# Sheet2.net
KiCad netlist of a schematic drawn in Altium Designer
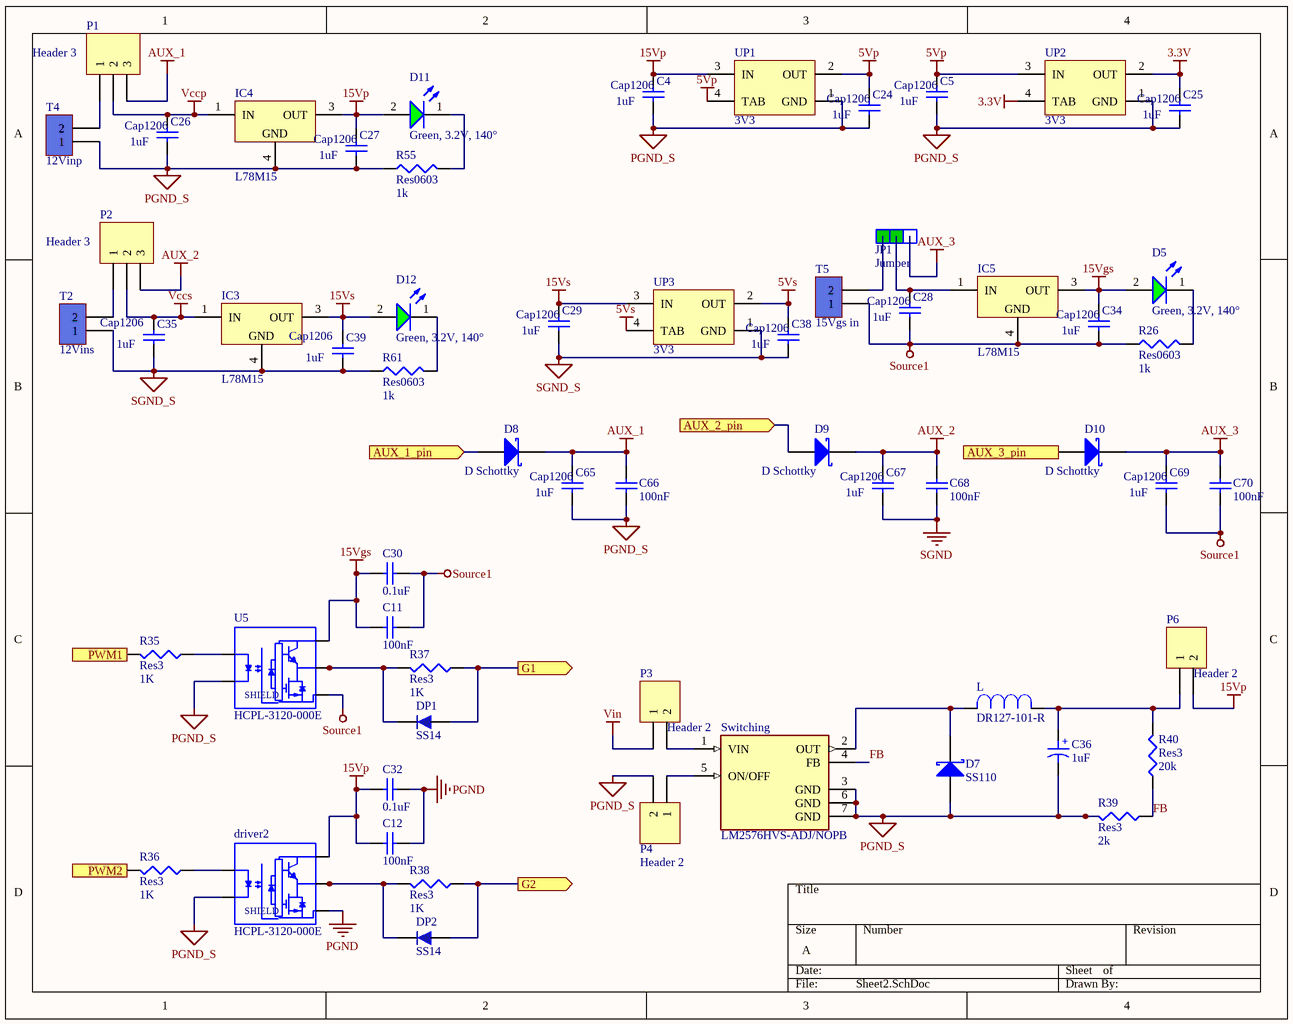
[diagram p0: Sheet2.SchDoc]

(export (version "E")
  (design (tool "Eeschema 10.0.6"))
  (components
    (comp (ref "C4")
      (value "Cap1206")
      (footprint "C1206")
      (description "CAP, CERM, 1uF, 50V, +/-20%, X7R, 1206")
      (fields (field (name "ALTIUM_VALUE") "1uF") (field (name "PUBLISHER") "Altium Limited"))
      (libsource (lib "Miscellaneous Devices") (part "Cap Semi"))
    )
    (comp (ref "C5")
      (value "Cap1206")
      (footprint "C1206")
      (description "CAP, CERM, 1uF, 50V, +/-20%, X7R, 1206")
      (fields (field (name "ALTIUM_VALUE") "1uF") (field (name "PUBLISHER") "Altium Limited"))
      (libsource (lib "Miscellaneous Devices") (part "Cap Semi"))
    )
    (comp (ref "C11")
      (value "100nF")
      (footprint "CAP0603")
      (description "TOTAL CAPACITOR SMD PACK")
      (fields (field (name "DESIGNER") "Abbas Basereh"))
      (libsource (lib "Altium_tehran") (part "CAP SMD PACKAGE"))
    )
    (comp (ref "C12")
      (value "100nF")
      (footprint "CAP0603")
      (description "TOTAL CAPACITOR SMD PACK")
      (fields (field (name "DESIGNER") "Abbas Basereh"))
      (libsource (lib "Altium_tehran") (part "CAP SMD PACKAGE"))
    )
    (comp (ref "C24")
      (value "Cap1206")
      (footprint "C1206")
      (description "CAP, CERM, 1uF, 50V, +/-20%, X7R, 1206")
      (fields (field (name "ALTIUM_VALUE") "1uF") (field (name "PUBLISHER") "Altium Limited"))
      (libsource (lib "Miscellaneous Devices") (part "Cap Semi"))
    )
    (comp (ref "C25")
      (value "Cap1206")
      (footprint "C1206")
      (description "CAP, CERM, 1uF, 50V, +/-20%, X7R, 1206")
      (fields (field (name "ALTIUM_VALUE") "1uF") (field (name "PUBLISHER") "Altium Limited"))
      (libsource (lib "Miscellaneous Devices") (part "Cap Semi"))
    )
    (comp (ref "C26")
      (value "Cap1206")
      (footprint "C1206")
      (description "CAP, CERM, 1uF, 50V, +/-20%, X7R, 1206")
      (fields (field (name "ALTIUM_VALUE") "1uF") (field (name "PUBLISHER") "Altium Limited"))
      (libsource (lib "Miscellaneous Devices") (part "Cap Semi"))
    )
    (comp (ref "C27")
      (value "Cap1206")
      (footprint "C1206")
      (description "CAP, CERM, 1uF, 50V, +/-20%, X7R, 1206")
      (fields (field (name "ALTIUM_VALUE") "1uF") (field (name "PUBLISHER") "Altium Limited"))
      (libsource (lib "Miscellaneous Devices") (part "Cap Semi"))
    )
    (comp (ref "C28")
      (value "Cap1206")
      (footprint "C1206")
      (description "CAP, CERM, 1uF, 50V, +/-20%, X7R, 1206")
      (fields (field (name "ALTIUM_VALUE") "1uF") (field (name "PUBLISHER") "Altium Limited"))
      (libsource (lib "Miscellaneous Devices") (part "Cap Semi"))
    )
    (comp (ref "C29")
      (value "Cap1206")
      (footprint "C1206")
      (description "CAP, CERM, 1uF, 50V, +/-20%, X7R, 1206")
      (fields (field (name "ALTIUM_VALUE") "1uF") (field (name "PUBLISHER") "Altium Limited"))
      (libsource (lib "Miscellaneous Devices") (part "Cap Semi"))
    )
    (comp (ref "C30")
      (value "0.1uF")
      (footprint "CAPC4817X12N")
      (description "CAP 1206")
      (fields (field (name "DESIGNER") "Abbas Basereh"))
      (libsource (lib "Altium_tehran") (part "CAP SMD 1206"))
    )
    (comp (ref "C32")
      (value "0.1uF")
      (footprint "CAPC4817X12N")
      (description "CAP 1206")
      (fields (field (name "DESIGNER") "Abbas Basereh"))
      (libsource (lib "Altium_tehran") (part "CAP SMD 1206"))
    )
    (comp (ref "C34")
      (value "Cap1206")
      (footprint "C1206")
      (description "CAP, CERM, 1uF, 50V, +/-20%, X7R, 1206")
      (fields (field (name "ALTIUM_VALUE") "1uF") (field (name "PUBLISHER") "Altium Limited"))
      (libsource (lib "Miscellaneous Devices") (part "Cap Semi"))
    )
    (comp (ref "C35")
      (value "Cap1206")
      (footprint "C1206")
      (description "CAP, CERM, 1uF, 50V, +/-20%, X7R, 1206")
      (fields (field (name "ALTIUM_VALUE") "1uF") (field (name "PUBLISHER") "Altium Limited"))
      (libsource (lib "Miscellaneous Devices") (part "Cap Semi"))
    )
    (comp (ref "C36")
      (value "1uF")
      (footprint "Cap electrolitic radial 8x12-3.5")
      (description "Cap electrolitic radial")
      (fields (field (name "DESIGNER") "Abbas Basereh"))
      (libsource (lib "Altium_tehran") (part "Cap ELECTROLITIC TOTAL SIZE"))
    )
    (comp (ref "C38")
      (value "Cap1206")
      (footprint "C1206")
      (description "CAP, CERM, 1uF, 50V, +/-20%, X7R, 1206")
      (fields (field (name "ALTIUM_VALUE") "1uF") (field (name "PUBLISHER") "Altium Limited"))
      (libsource (lib "Miscellaneous Devices") (part "Cap Semi"))
    )
    (comp (ref "C39")
      (value "Cap1206")
      (footprint "C1206")
      (description "CAP, CERM, 1uF, 50V, +/-20%, X7R, 1206")
      (fields (field (name "ALTIUM_VALUE") "1uF") (field (name "PUBLISHER") "Altium Limited"))
      (libsource (lib "Miscellaneous Devices") (part "Cap Semi"))
    )
    (comp (ref "C65")
      (value "Cap1206")
      (footprint "C1206")
      (description "CAP, CERM, 1uF, 50V, +/-20%, X7R, 1206")
      (fields (field (name "ALTIUM_VALUE") "1uF") (field (name "PUBLISHER") "Altium Limited"))
      (libsource (lib "Miscellaneous Devices") (part "Cap Semi"))
    )
    (comp (ref "C66")
      (value "100nF")
      (footprint "Cap SMD 100UF 35~50v")
      (description "TOTAL CAPACITOR SMD PACK")
      (fields (field (name "DESIGNER") "Abbas Basereh"))
      (libsource (lib "Altium_tehran") (part "CAP SMD PACKAGE"))
    )
    (comp (ref "C67")
      (value "Cap1206")
      (footprint "C1206")
      (description "CAP, CERM, 1uF, 50V, +/-20%, X7R, 1206")
      (fields (field (name "ALTIUM_VALUE") "1uF") (field (name "PUBLISHER") "Altium Limited"))
      (libsource (lib "Miscellaneous Devices") (part "Cap Semi"))
    )
    (comp (ref "C68")
      (value "100nF")
      (footprint "Cap SMD 100UF 35~50v")
      (description "TOTAL CAPACITOR SMD PACK")
      (fields (field (name "DESIGNER") "Abbas Basereh"))
      (libsource (lib "Altium_tehran") (part "CAP SMD PACKAGE"))
    )
    (comp (ref "C69")
      (value "Cap1206")
      (footprint "C1206")
      (description "CAP, CERM, 1uF, 50V, +/-20%, X7R, 1206")
      (fields (field (name "ALTIUM_VALUE") "1uF") (field (name "PUBLISHER") "Altium Limited"))
      (libsource (lib "Miscellaneous Devices") (part "Cap Semi"))
    )
    (comp (ref "C70")
      (value "100nF")
      (footprint "Cap SMD 100UF 35~50v")
      (description "TOTAL CAPACITOR SMD PACK")
      (fields (field (name "DESIGNER") "Abbas Basereh"))
      (libsource (lib "Altium_tehran") (part "CAP SMD PACKAGE"))
    )
    (comp (ref "D5")
      (value "Green, 3.2V, 140°")
      (footprint "WL-SMCW_0805_150080xx75000")
      (description "WL-SMCW Mono-color Chip LED Waterclear, SMT, size 0805, Green, 3.2V, 140°")
      (fields
        (field (name "MANUFACTURER PART NUMBER") "150080GS75000")
        (field (name "MANUFACTURER") "Wurth Elektronik")
      )
      (libsource (lib "150060AS75000_Altium_WL-SMCW_rev24b") (part "150080GS75000"))
    )
    (comp (ref "D7")
      (value "SS110")
      (footprint "SMB")
      (description "Schottky Diode")
      (fields (field (name "PUBLISHER") "Altium Limited"))
      (libsource (lib "Miscellaneous Devices") (part "D Schottky"))
    )
    (comp (ref "D8")
      (value "D Schottky")
      (footprint "SMB")
      (description "Schottky Diode")
      (fields (field (name "PUBLISHER") "Altium Limited"))
      (libsource (lib "Miscellaneous Devices") (part "D Schottky"))
    )
    (comp (ref "D9")
      (value "D Schottky")
      (footprint "SMB")
      (description "Schottky Diode")
      (fields (field (name "PUBLISHER") "Altium Limited"))
      (libsource (lib "Miscellaneous Devices") (part "D Schottky"))
    )
    (comp (ref "D10")
      (value "D Schottky")
      (footprint "SMB")
      (description "Schottky Diode")
      (fields (field (name "PUBLISHER") "Altium Limited"))
      (libsource (lib "Miscellaneous Devices") (part "D Schottky"))
    )
    (comp (ref "D11")
      (value "Green, 3.2V, 140°")
      (footprint "WL-SMCW_0805_150080xx75000")
      (description "WL-SMCW Mono-color Chip LED Waterclear, SMT, size 0805, Green, 3.2V, 140°")
      (fields
        (field (name "MANUFACTURER PART NUMBER") "150080GS75000")
        (field (name "MANUFACTURER") "Wurth Elektronik")
      )
      (libsource (lib "150060AS75000_Altium_WL-SMCW_rev24b") (part "150080GS75000"))
    )
    (comp (ref "D12")
      (value "Green, 3.2V, 140°")
      (footprint "WL-SMCW_0805_150080xx75000")
      (description "WL-SMCW Mono-color Chip LED Waterclear, SMT, size 0805, Green, 3.2V, 140°")
      (fields
        (field (name "MANUFACTURER PART NUMBER") "150080GS75000")
        (field (name "MANUFACTURER") "Wurth Elektronik")
      )
      (libsource (lib "150060AS75000_Altium_WL-SMCW_rev24b") (part "150080GS75000"))
    )
    (comp (ref "DP1")
      (value "SS14")
      (footprint "430X270D")
      (description "Schottkey Rectifiers")
      (fields (field (name "DESIGNER") "Abbas Basereh"))
      (libsource (lib "Altium_tehran") (part "1N5819"))
    )
    (comp (ref "DP2")
      (value "SS14")
      (footprint "430X270D")
      (description "Schottkey Rectifiers")
      (fields (field (name "DESIGNER") "Abbas Basereh"))
      (libsource (lib "Altium_tehran") (part "1N5819"))
    )
    (comp (ref "driver2")
      (value "HCPL-3120-000E")
      (footprint "DIP762W65P254L990H470Q8")
      (description "2.5A Gate Driver Optical Coupling 3750Vrms 1 Channel 8-DIP")
      (fields (field (name "MF") "Broadcom Limited"))
      (libsource (lib "HCPL-3120-000E") (part "HCPL-3120-000E"))
    )
    (comp (ref "IC3")
      (value "L78M15")
      (footprint "TO-252")
      (description "Precision 500mA Regulator")
      (libsource (lib "Altium_tehran") (part "L78M05"))
    )
    (comp (ref "IC4")
      (value "L78M15")
      (footprint "TO-252")
      (description "Precision 500mA Regulator")
      (libsource (lib "Altium_tehran") (part "L78M05"))
    )
    (comp (ref "IC5")
      (value "L78M15")
      (footprint "TO-252")
      (description "Precision 500mA Regulator")
      (libsource (lib "Altium_tehran") (part "L78M05"))
    )
    (comp (ref "JP1")
      (value "Jumper")
      (footprint "jumper selector")
      (description "Jumper Selector")
      (libsource (lib "Altium_tehran") (part "Jumper Selector"))
    )
    (comp (ref "L")
      (value "DR127-101-R")
      (footprint "INDM125125X800N")
      (description "100ÂµH Shielded Wirewound Inductor 1.96A 163mOhm Nonstandard")
      (fields (field (name "MF") "Eaton"))
      (libsource (lib "DR127-101-R") (part "DR127-101-R"))
    )
    (comp (ref "P1")
      (value "Header 3")
      (footprint "HDR1X3")
      (description "Header, 3-Pin")
      (fields (field (name "PUBLISHER") "Altium Limited"))
      (libsource (lib "Altium_tehran") (part "Header 3"))
    )
    (comp (ref "P2")
      (value "Header 3")
      (footprint "HDR1X3")
      (description "Header, 3-Pin")
      (fields (field (name "PUBLISHER") "Altium Limited"))
      (libsource (lib "Altium_tehran") (part "Header 3"))
    )
    (comp (ref "P3")
      (value "Header 2")
      (footprint "HDR1X2")
      (description "Header, 2-Pin, 100mill")
      (fields (field (name "PUBLISHER") "Altium Limited"))
      (libsource (lib "Miscellaneous Connectors") (part "Header 2"))
    )
    (comp (ref "P4")
      (value "Header 2")
      (footprint "HDR1X2")
      (description "Header, 2-Pin, 100mill")
      (fields (field (name "PUBLISHER") "Altium Limited"))
      (libsource (lib "") (part "Header 2_1"))
    )
    (comp (ref "P6")
      (value "Header 2")
      (footprint "HDR1X2")
      (description "Header, 2-Pin, 100mill")
      (fields (field (name "PUBLISHER") "Altium Limited"))
      (libsource (lib "Miscellaneous Connectors") (part "Header 2"))
    )
    (comp (ref "R26")
      (value "Res0603")
      (footprint "J1-0603")
      (description "RES, 1k ohm, 1%, 0.1W, 0603")
      (fields (field (name "ALTIUM_VALUE") "1k") (field (name "PUBLISHER") "Altium Limited"))
      (libsource (lib "Miscellaneous Devices") (part "Res3"))
    )
    (comp (ref "R35")
      (value "Res3")
      (footprint "J1-0603")
      (description "Resistor")
      (fields (field (name "ALTIUM_VALUE") "1K") (field (name "PUBLISHER") "Altium Limited"))
      (libsource (lib "Miscellaneous Devices") (part "Res3"))
    )
    (comp (ref "R36")
      (value "Res3")
      (footprint "J1-0603")
      (description "Resistor")
      (fields (field (name "ALTIUM_VALUE") "1K") (field (name "PUBLISHER") "Altium Limited"))
      (libsource (lib "Miscellaneous Devices") (part "Res3"))
    )
    (comp (ref "R37")
      (value "Res3")
      (footprint "J1-0603")
      (description "Resistor")
      (fields (field (name "ALTIUM_VALUE") "1K") (field (name "PUBLISHER") "Altium Limited"))
      (libsource (lib "Miscellaneous Devices") (part "Res3"))
    )
    (comp (ref "R38")
      (value "Res3")
      (footprint "J1-0603")
      (description "Resistor")
      (fields (field (name "ALTIUM_VALUE") "1K") (field (name "PUBLISHER") "Altium Limited"))
      (libsource (lib "Miscellaneous Devices") (part "Res3"))
    )
    (comp (ref "R39")
      (value "Res3")
      (footprint "J1-0603")
      (description "Resistor")
      (fields (field (name "ALTIUM_VALUE") "2k") (field (name "PUBLISHER") "Altium Limited"))
      (libsource (lib "Miscellaneous Devices") (part "Res3"))
    )
    (comp (ref "R40")
      (value "Res3")
      (footprint "J1-0603")
      (description "Resistor")
      (fields (field (name "ALTIUM_VALUE") "20k") (field (name "PUBLISHER") "Altium Limited"))
      (libsource (lib "Miscellaneous Devices") (part "Res3"))
    )
    (comp (ref "R55")
      (value "Res0603")
      (footprint "J1-0603")
      (description "RES, 1k ohm, 1%, 0.1W, 0603")
      (fields (field (name "ALTIUM_VALUE") "1k") (field (name "PUBLISHER") "Altium Limited"))
      (libsource (lib "Miscellaneous Devices") (part "Res3"))
    )
    (comp (ref "R61")
      (value "Res0603")
      (footprint "J1-0603")
      (description "RES, 1k ohm, 1%, 0.1W, 0603")
      (fields (field (name "ALTIUM_VALUE") "1k") (field (name "PUBLISHER") "Altium Limited"))
      (libsource (lib "Miscellaneous Devices") (part "Res3"))
    )
    (comp (ref "Switching")
      (value "LM2576HVS-ADJ/NOPB")
      (footprint "REG_LM2576HVS-ADJ/NOPB")
      (fields (field (name "MF") "Texas Instruments"))
      (libsource (lib "LM2576HVS-ADJ_NOPB") (part "LM2576HVS-ADJ/NOPB"))
    )
    (comp (ref "T2")
      (value "12Vins")
      (footprint "KF301 2PIN")
      (description "Terminal 2 Pin 250VAC 16A")
      (fields (field (name "DESIGNER") "Abbas Basereh"))
      (libsource (lib "Altium_tehran") (part "KF301-2Pin_Terminal"))
    )
    (comp (ref "T4")
      (value "12Vinp")
      (footprint "KF301 2PIN")
      (description "Terminal 2 Pin 250VAC 16A")
      (fields (field (name "DESIGNER") "Abbas Basereh"))
      (libsource (lib "Altium_tehran") (part "KF301-2Pin_Terminal"))
    )
    (comp (ref "T5")
      (value "15Vgs in")
      (footprint "KF301 2PIN")
      (description "Terminal 2 Pin 250VAC 16A")
      (fields (field (name "DESIGNER") "Abbas Basereh"))
      (libsource (lib "Altium_tehran") (part "KF301-2Pin_Terminal"))
    )
    (comp (ref "U5")
      (value "HCPL-3120-000E")
      (footprint "DIP762W65P254L990H470Q8")
      (description "2.5A Gate Driver Optical Coupling 3750Vrms 1 Channel 8-DIP")
      (fields (field (name "MF") "Broadcom Limited"))
      (libsource (lib "HCPL-3120-000E") (part "HCPL-3120-000E"))
    )
    (comp (ref "UP1")
      (value "3V3")
      (footprint "SOT223")
      (description "x.x Volt, 800mA Low-Dropout Linear Regulator, 4-pin SOT-223")
      (fields (field (name "DESIGNER") "Ali Hafizi"))
      (libsource (lib "Altium_tehran") (part "AMS1117-x.x"))
    )
    (comp (ref "UP2")
      (value "3V3")
      (footprint "SOT223")
      (description "x.x Volt, 800mA Low-Dropout Linear Regulator, 4-pin SOT-223")
      (fields (field (name "DESIGNER") "Ali Hafizi"))
      (libsource (lib "Altium_tehran") (part "AMS1117-x.x"))
    )
    (comp (ref "UP3")
      (value "3V3")
      (footprint "SOT223")
      (description "x.x Volt, 800mA Low-Dropout Linear Regulator, 4-pin SOT-223")
      (fields (field (name "DESIGNER") "Ali Hafizi"))
      (libsource (lib "Altium_tehran") (part "AMS1117-x.x"))
    )
  )
  (nets
    (net (code "1") (name "/AUX_1_pin") (class "Default")
      (node (ref "D8") (pin "1") (pinfunction "A_1") (pintype "passive"))
    )
    (net (code "2") (name "/AUX_2_pin") (class "Default")
      (node (ref "D9") (pin "1") (pinfunction "A_1") (pintype "passive"))
    )
    (net (code "3") (name "/AUX_3_pin") (class "Default")
      (node (ref "D10") (pin "1") (pinfunction "A_1") (pintype "passive"))
    )
    (net (code "4") (name "/FB") (class "Default")
      (node (ref "R39") (pin "1") (pinfunction "1_1") (pintype "passive"))
      (node (ref "R40") (pin "1") (pinfunction "1_1") (pintype "passive"))
      (node (ref "Switching") (pin "4") (pinfunction "FB_4") (pintype "passive"))
    )
    (net (code "5") (name "/G1") (class "Default")
      (node (ref "DP1") (pin "1") (pintype "passive"))
      (node (ref "R37") (pin "1") (pinfunction "1_1") (pintype "passive"))
    )
    (net (code "6") (name "/G2") (class "Default")
      (node (ref "DP2") (pin "1") (pintype "passive"))
      (node (ref "R38") (pin "1") (pinfunction "1_1") (pintype "passive"))
    )
    (net (code "7") (name "/PWM1") (class "Default")
      (node (ref "R35") (pin "2") (pinfunction "2_2") (pintype "passive"))
    )
    (net (code "8") (name "/PWM2") (class "Default")
      (node (ref "R36") (pin "2") (pinfunction "2_2") (pintype "passive"))
    )
    (net (code "9") (name "3.3V") (class "Default")
      (node (ref "C25") (pin "1") (pinfunction "1_1") (pintype "passive"))
      (node (ref "UP2") (pin "2") (pinfunction "OUT_2") (pintype "power_in"))
      (node (ref "UP2") (pin "4") (pinfunction "TAB_4") (pintype "power_in"))
    )
    (net (code "10") (name "5Vp") (class "Default")
      (node (ref "C24") (pin "1") (pinfunction "1_1") (pintype "passive"))
      (node (ref "C5") (pin "1") (pinfunction "1_1") (pintype "passive"))
      (node (ref "UP1") (pin "2") (pinfunction "OUT_2") (pintype "power_in"))
      (node (ref "UP1") (pin "4") (pinfunction "TAB_4") (pintype "power_in"))
      (node (ref "UP2") (pin "3") (pinfunction "IN_3") (pintype "power_in"))
    )
    (net (code "11") (name "5Vs") (class "Default")
      (node (ref "C38") (pin "1") (pinfunction "1_1") (pintype "passive"))
      (node (ref "UP3") (pin "2") (pinfunction "OUT_2") (pintype "power_in"))
      (node (ref "UP3") (pin "4") (pinfunction "TAB_4") (pintype "power_in"))
    )
    (net (code "12") (name "15Vgs") (class "Default")
      (node (ref "C11") (pin "2") (pinfunction "2_2") (pintype "passive"))
      (node (ref "C30") (pin "2") (pinfunction "2_2") (pintype "passive"))
      (node (ref "C34") (pin "1") (pinfunction "1_1") (pintype "passive"))
      (node (ref "D5") (pin "2") (pinfunction "A_2") (pintype "passive"))
      (node (ref "IC5") (pin "3") (pinfunction "OUT_3") (pintype "power_in"))
      (node (ref "U5") (pin "8") (pinfunction "VCC_8") (pintype "passive"))
    )
    (net (code "13") (name "15Vp") (class "Default")
      (node (ref "C12") (pin "2") (pinfunction "2_2") (pintype "passive"))
      (node (ref "C27") (pin "1") (pinfunction "1_1") (pintype "passive"))
      (node (ref "C32") (pin "2") (pinfunction "2_2") (pintype "passive"))
      (node (ref "C4") (pin "1") (pinfunction "1_1") (pintype "passive"))
      (node (ref "D11") (pin "2") (pinfunction "A_2") (pintype "passive"))
      (node (ref "IC4") (pin "3") (pinfunction "OUT_3") (pintype "power_in"))
      (node (ref "P6") (pin "2") (pinfunction "2_2") (pintype "passive"))
      (node (ref "UP1") (pin "3") (pinfunction "IN_3") (pintype "power_in"))
      (node (ref "driver2") (pin "8") (pinfunction "VCC_8") (pintype "passive"))
    )
    (net (code "14") (name "15Vs") (class "Default")
      (node (ref "C29") (pin "1") (pinfunction "1_1") (pintype "passive"))
      (node (ref "C39") (pin "1") (pinfunction "1_1") (pintype "passive"))
      (node (ref "D12") (pin "2") (pinfunction "A_2") (pintype "passive"))
      (node (ref "IC3") (pin "3") (pinfunction "OUT_3") (pintype "power_in"))
      (node (ref "UP3") (pin "3") (pinfunction "IN_3") (pintype "power_in"))
    )
    (net (code "15") (name "AUX_1") (class "Default")
      (node (ref "C65") (pin "1") (pinfunction "1_1") (pintype "passive"))
      (node (ref "C66") (pin "2") (pinfunction "2_2") (pintype "passive"))
      (node (ref "D8") (pin "2") (pinfunction "K_2") (pintype "passive"))
      (node (ref "P1") (pin "3") (pinfunction "3_3") (pintype "passive"))
    )
    (net (code "16") (name "AUX_2") (class "Default")
      (node (ref "C67") (pin "1") (pinfunction "1_1") (pintype "passive"))
      (node (ref "C68") (pin "2") (pinfunction "2_2") (pintype "passive"))
      (node (ref "D9") (pin "2") (pinfunction "K_2") (pintype "passive"))
      (node (ref "P2") (pin "3") (pinfunction "3_3") (pintype "passive"))
    )
    (net (code "17") (name "AUX_3") (class "Default")
      (node (ref "C69") (pin "1") (pinfunction "1_1") (pintype "passive"))
      (node (ref "C70") (pin "2") (pinfunction "2_2") (pintype "passive"))
      (node (ref "D10") (pin "2") (pinfunction "K_2") (pintype "passive"))
      (node (ref "JP1") (pin "3") (pinfunction "3_3") (pintype "passive"))
    )
    (net (code "18") (name "Net-(C36-Pad1)") (class "Default")
      (node (ref "C36") (pin "1") (pinfunction "1_1") (pintype "passive"))
      (node (ref "L") (pin "1") (pinfunction "1_1") (pintype "passive"))
      (node (ref "P6") (pin "1") (pinfunction "1_1") (pintype "passive"))
      (node (ref "R40") (pin "2") (pinfunction "2_2") (pintype "passive"))
    )
    (net (code "19") (name "Net-(D5-K)") (class "Default")
      (node (ref "D5") (pin "1") (pinfunction "K_1") (pintype "passive"))
      (node (ref "R26") (pin "2") (pinfunction "2_2") (pintype "passive"))
    )
    (net (code "20") (name "Net-(D7-K)") (class "Default")
      (node (ref "D7") (pin "2") (pinfunction "K_2") (pintype "passive"))
      (node (ref "L") (pin "2") (pinfunction "2_2") (pintype "passive"))
      (node (ref "Switching") (pin "2") (pinfunction "OUT_2") (pintype "output"))
    )
    (net (code "21") (name "Net-(D11-K)") (class "Default")
      (node (ref "D11") (pin "1") (pinfunction "K_1") (pintype "passive"))
      (node (ref "R55") (pin "2") (pinfunction "2_2") (pintype "passive"))
    )
    (net (code "22") (name "Net-(D12-K)") (class "Default")
      (node (ref "D12") (pin "1") (pinfunction "K_1") (pintype "passive"))
      (node (ref "R61") (pin "2") (pinfunction "2_2") (pintype "passive"))
    )
    (net (code "23") (name "Net-(DP1-Pad2)") (class "Default")
      (node (ref "DP1") (pin "2") (pintype "passive"))
      (node (ref "R37") (pin "2") (pinfunction "2_2") (pintype "passive"))
      (node (ref "U5") (pin "6") (pinfunction "VO_6") (pintype "passive"))
      (node (ref "U5") (pin "7") (pinfunction "VO_7") (pintype "passive"))
    )
    (net (code "24") (name "Net-(DP2-Pad2)") (class "Default")
      (node (ref "DP2") (pin "2") (pintype "passive"))
      (node (ref "R38") (pin "2") (pinfunction "2_2") (pintype "passive"))
      (node (ref "driver2") (pin "6") (pinfunction "VO_6") (pintype "passive"))
      (node (ref "driver2") (pin "7") (pinfunction "VO_7") (pintype "passive"))
    )
    (net (code "25") (name "Net-(IC5-IN)") (class "Default")
      (node (ref "C28") (pin "1") (pinfunction "1_1") (pintype "passive"))
      (node (ref "IC5") (pin "1") (pinfunction "IN_1") (pintype "power_in"))
      (node (ref "JP1") (pin "2") (pinfunction "2_2") (pintype "passive"))
    )
    (net (code "26") (name "Net-(JP1-Pad1)") (class "Default")
      (node (ref "JP1") (pin "1") (pinfunction "1_1") (pintype "passive"))
      (node (ref "T5") (pin "2") (pinfunction "2_2") (pintype "passive"))
    )
    (net (code "27") (name "Net-(P1-Pad1)") (class "Default")
      (node (ref "P1") (pin "1") (pinfunction "1_1") (pintype "passive"))
      (node (ref "T4") (pin "2") (pinfunction "2_2") (pintype "passive"))
    )
    (net (code "28") (name "Net-(P2-Pad1)") (class "Default")
      (node (ref "P2") (pin "1") (pinfunction "1_1") (pintype "passive"))
      (node (ref "T2") (pin "2") (pinfunction "2_2") (pintype "passive"))
    )
    (net (code "29") (name "Net-(Switching-ON{slash}OFF)") (class "Default")
      (node (ref "P4") (pin "1") (pinfunction "1_1") (pintype "passive"))
      (node (ref "Switching") (pin "5") (pinfunction "ON/OFF_5") (pintype "input"))
    )
    (net (code "30") (name "Net-(Switching-VIN)") (class "Default")
      (node (ref "P3") (pin "2") (pinfunction "2_2") (pintype "passive"))
      (node (ref "Switching") (pin "1") (pinfunction "VIN_1") (pintype "input"))
    )
    (net (code "31") (name "Net-(U5-ANODE)") (class "Default")
      (node (ref "R35") (pin "1") (pinfunction "1_1") (pintype "passive"))
      (node (ref "U5") (pin "2") (pinfunction "ANODE_2") (pintype "passive"))
    )
    (net (code "32") (name "Net-(driver2-ANODE)") (class "Default")
      (node (ref "R36") (pin "1") (pinfunction "1_1") (pintype "passive"))
      (node (ref "driver2") (pin "2") (pinfunction "ANODE_2") (pintype "passive"))
    )
    (net (code "33") (name "PGND") (class "Default")
      (node (ref "C12") (pin "1") (pinfunction "1_1") (pintype "passive"))
      (node (ref "C32") (pin "1") (pinfunction "1_1") (pintype "passive"))
      (node (ref "driver2") (pin "5") (pinfunction "VEE_5") (pintype "passive"))
    )
    (net (code "34") (name "PGND_S") (class "Default")
      (node (ref "C24") (pin "2") (pinfunction "2_2") (pintype "passive"))
      (node (ref "C25") (pin "2") (pinfunction "2_2") (pintype "passive"))
      (node (ref "C26") (pin "2") (pinfunction "2_2") (pintype "passive"))
      (node (ref "C27") (pin "2") (pinfunction "2_2") (pintype "passive"))
      (node (ref "C36") (pin "2") (pinfunction "2_2") (pintype "passive"))
      (node (ref "C4") (pin "2") (pinfunction "2_2") (pintype "passive"))
      (node (ref "C5") (pin "2") (pinfunction "2_2") (pintype "passive"))
      (node (ref "C65") (pin "2") (pinfunction "2_2") (pintype "passive"))
      (node (ref "C66") (pin "1") (pinfunction "1_1") (pintype "passive"))
      (node (ref "D7") (pin "1") (pinfunction "A_1") (pintype "passive"))
      (node (ref "IC4") (pin "4") (pinfunction "GND_4") (pintype "power_in"))
      (node (ref "P4") (pin "2") (pinfunction "2_2") (pintype "passive"))
      (node (ref "R39") (pin "2") (pinfunction "2_2") (pintype "passive"))
      (node (ref "R55") (pin "1") (pinfunction "1_1") (pintype "passive"))
      (node (ref "Switching") (pin "3") (pinfunction "GND_3") (pintype "power_in"))
      (node (ref "Switching") (pin "6") (pinfunction "GND_6") (pintype "power_in"))
      (node (ref "Switching") (pin "7") (pinfunction "GND_7") (pintype "power_in"))
      (node (ref "T4") (pin "1") (pinfunction "1_1") (pintype "passive"))
      (node (ref "U5") (pin "3") (pinfunction "CATHODE_3") (pintype "passive"))
      (node (ref "UP1") (pin "1") (pinfunction "GND_1") (pintype "power_in"))
      (node (ref "UP2") (pin "1") (pinfunction "GND_1") (pintype "power_in"))
      (node (ref "driver2") (pin "3") (pinfunction "CATHODE_3") (pintype "passive"))
    )
    (net (code "35") (name "SGND") (class "Default")
      (node (ref "C67") (pin "2") (pinfunction "2_2") (pintype "passive"))
      (node (ref "C68") (pin "1") (pinfunction "1_1") (pintype "passive"))
    )
    (net (code "36") (name "SGND_S") (class "Default")
      (node (ref "C29") (pin "2") (pinfunction "2_2") (pintype "passive"))
      (node (ref "C35") (pin "2") (pinfunction "2_2") (pintype "passive"))
      (node (ref "C38") (pin "2") (pinfunction "2_2") (pintype "passive"))
      (node (ref "C39") (pin "2") (pinfunction "2_2") (pintype "passive"))
      (node (ref "IC3") (pin "4") (pinfunction "GND_4") (pintype "power_in"))
      (node (ref "R61") (pin "1") (pinfunction "1_1") (pintype "passive"))
      (node (ref "T2") (pin "1") (pinfunction "1_1") (pintype "passive"))
      (node (ref "UP3") (pin "1") (pinfunction "GND_1") (pintype "power_in"))
    )
    (net (code "37") (name "Source1") (class "Default")
      (node (ref "C11") (pin "1") (pinfunction "1_1") (pintype "passive"))
      (node (ref "C28") (pin "2") (pinfunction "2_2") (pintype "passive"))
      (node (ref "C30") (pin "1") (pinfunction "1_1") (pintype "passive"))
      (node (ref "C34") (pin "2") (pinfunction "2_2") (pintype "passive"))
      (node (ref "C69") (pin "2") (pinfunction "2_2") (pintype "passive"))
      (node (ref "C70") (pin "1") (pinfunction "1_1") (pintype "passive"))
      (node (ref "IC5") (pin "4") (pinfunction "GND_4") (pintype "power_in"))
      (node (ref "R26") (pin "1") (pinfunction "1_1") (pintype "passive"))
      (node (ref "T5") (pin "1") (pinfunction "1_1") (pintype "passive"))
      (node (ref "U5") (pin "5") (pinfunction "VEE_5") (pintype "passive"))
    )
    (net (code "38") (name "Vccp") (class "Default")
      (node (ref "C26") (pin "1") (pinfunction "1_1") (pintype "passive"))
      (node (ref "IC4") (pin "1") (pinfunction "IN_1") (pintype "power_in"))
      (node (ref "P1") (pin "2") (pinfunction "2_2") (pintype "passive"))
    )
    (net (code "39") (name "Vccs") (class "Default")
      (node (ref "C35") (pin "1") (pinfunction "1_1") (pintype "passive"))
      (node (ref "IC3") (pin "1") (pinfunction "IN_1") (pintype "power_in"))
      (node (ref "P2") (pin "2") (pinfunction "2_2") (pintype "passive"))
    )
    (net (code "40") (name "Vin") (class "Default")
      (node (ref "P3") (pin "1") (pinfunction "1_1") (pintype "passive"))
    )
  )
)
